# SCH_EDR_Project_2023-04-17.net
KiCad netlist of a schematic drawn in EasyEDA
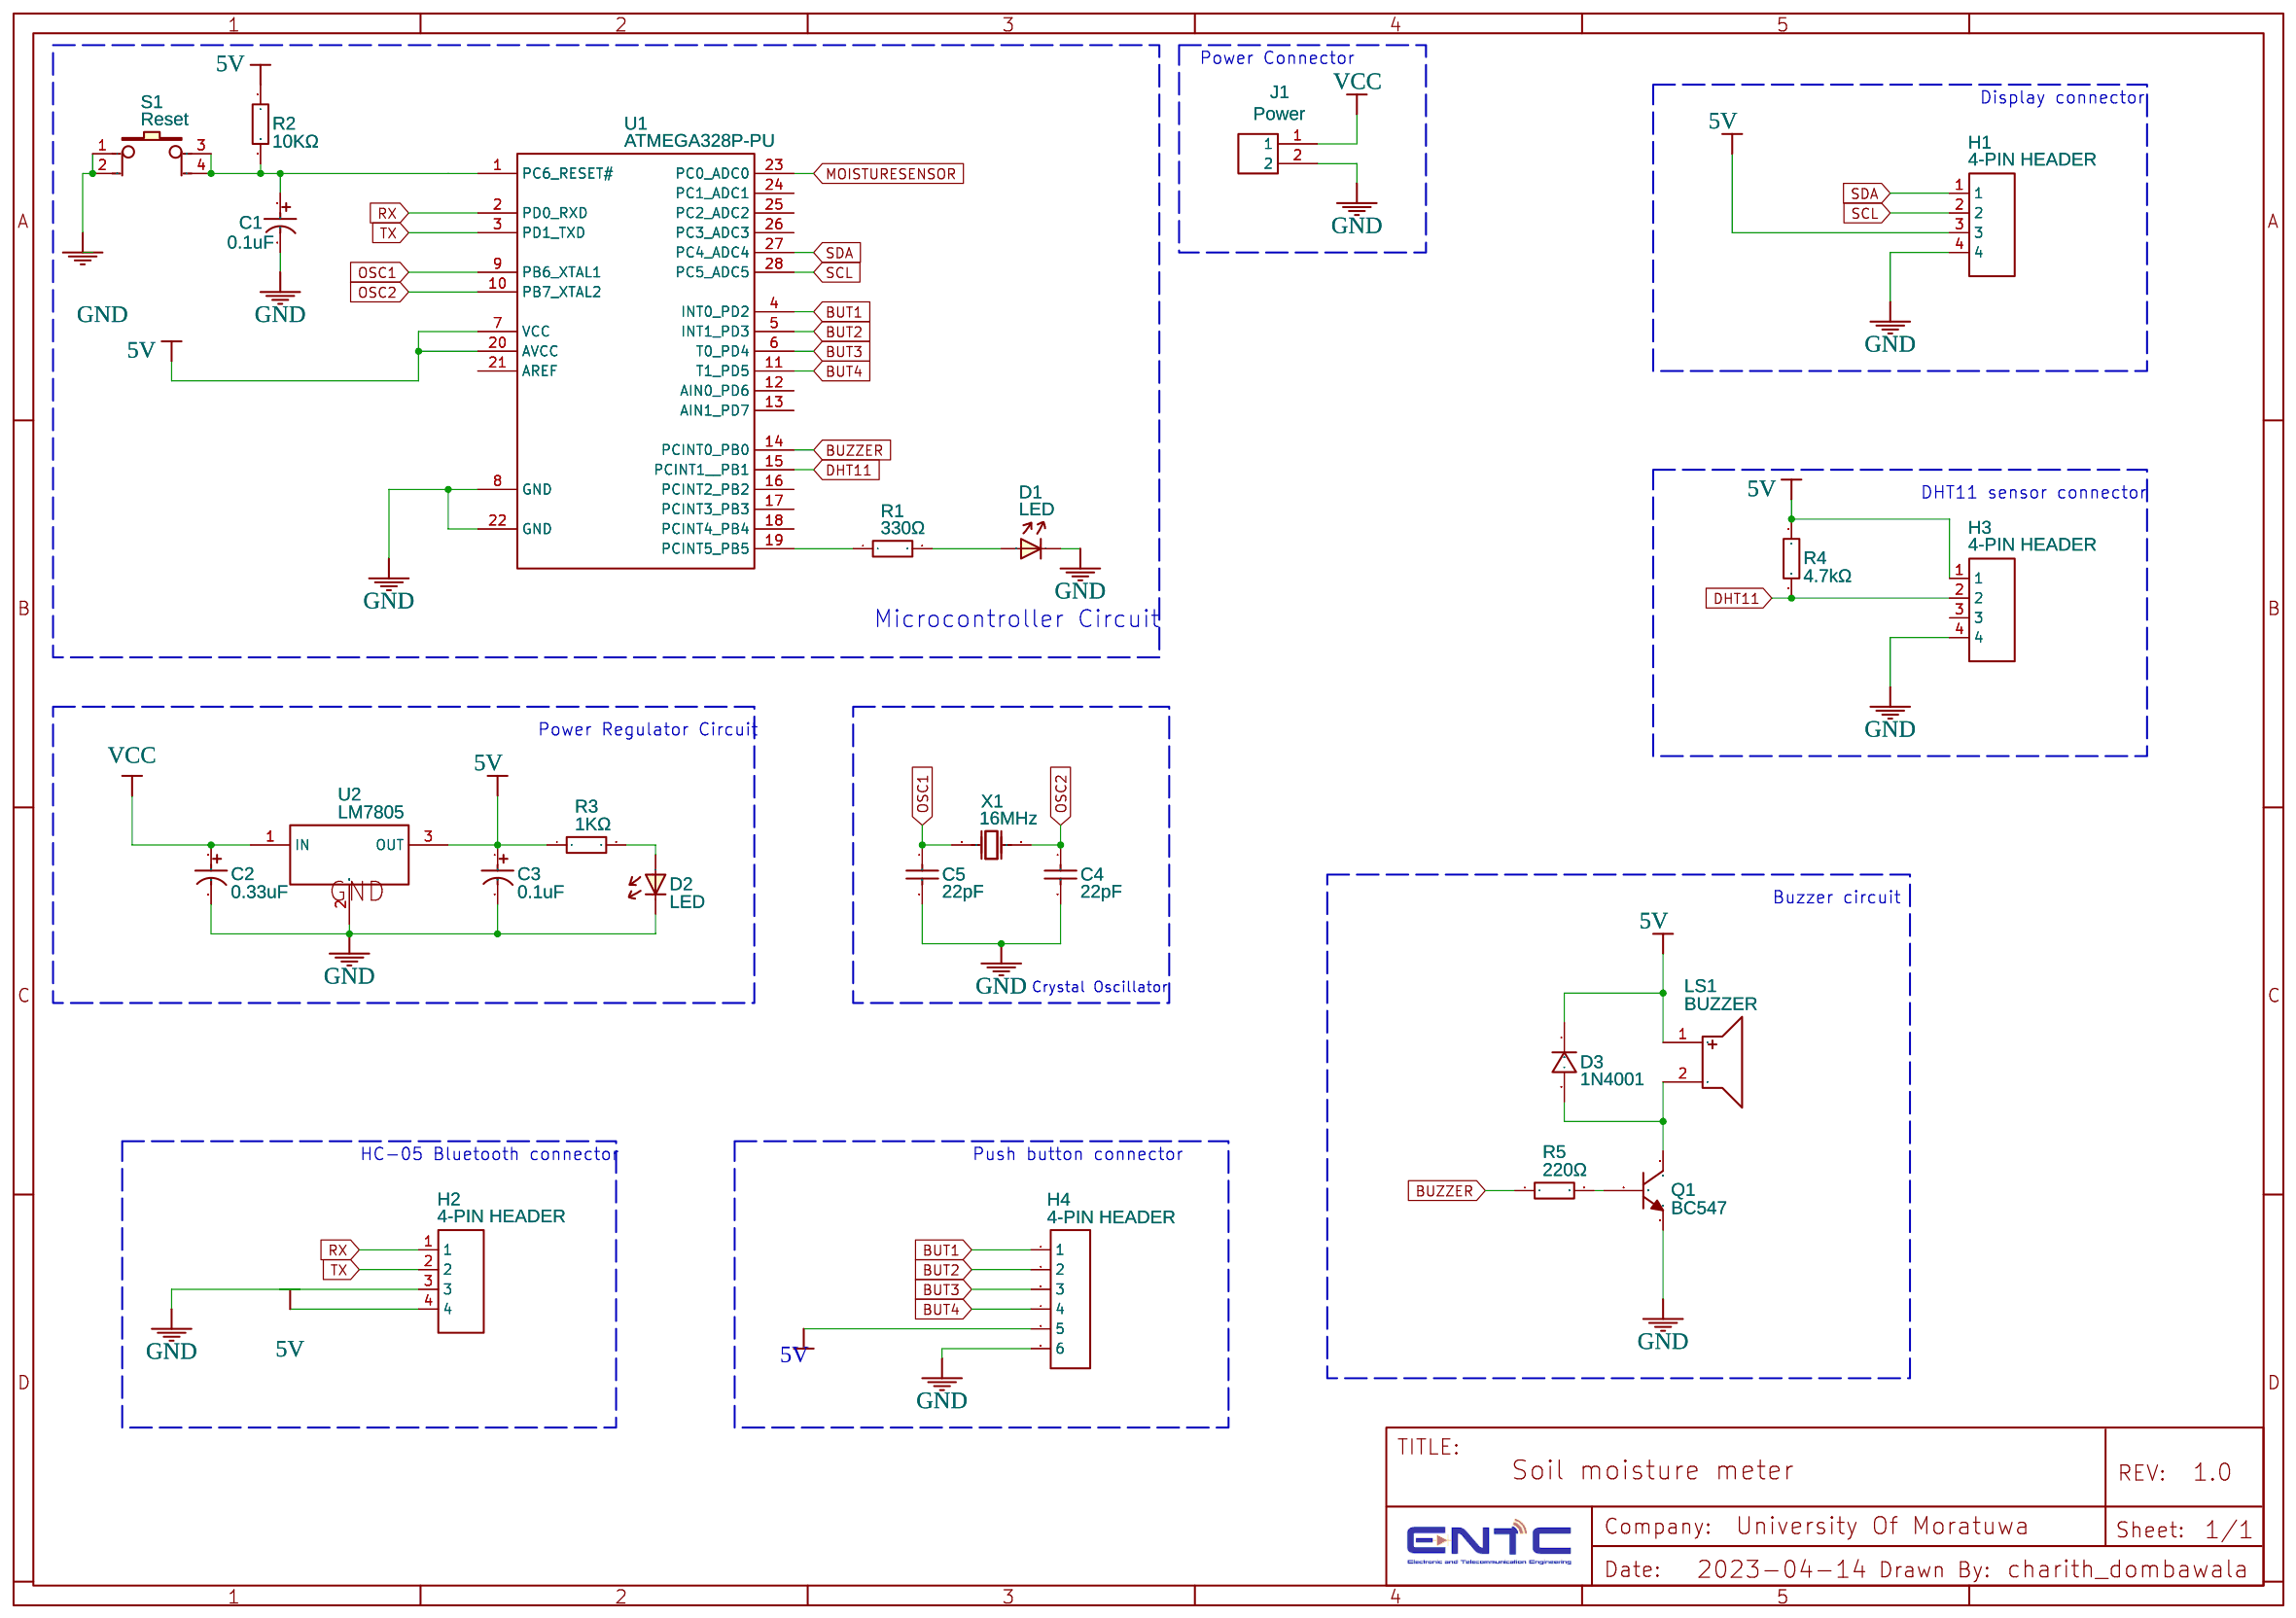
[diagram p0: schematic sheet]

(export (version "E")
  (design (tool "Eeschema 10.0.6"))
  (components
    (comp (ref "C1")
      (value "0.1uF")
      (fields (field (name "BOM_Manufacturer Part") "0.1UF 50V") (field (name "BOM_Supplier Part") "C28061"))
      (libsource (lib "") (part "0.1uF"))
    )
    (comp (ref "C2")
      (value "0.33uF")
      (fields
        (field (name "BOM_Manufacturer Part") "0.33uF 50V 5*11")
        (field (name "BOM_Supplier Part") "C45097")
      )
      (libsource (lib "") (part "0.33uF"))
    )
    (comp (ref "C3")
      (value "0.1uF")
      (fields (field (name "BOM_Manufacturer Part") "0.1UF 50V") (field (name "BOM_Supplier Part") "C28061"))
      (libsource (lib "") (part "0.1uF"))
    )
    (comp (ref "C4")
      (value "22pF")
      (fields
        (field (name "BOM_Manufacturer Part") "22pf/50V 10%")
        (field (name "BOM_Supplier Part") "C9316")
      )
      (libsource (lib "") (part "22pf/50V 10%"))
    )
    (comp (ref "C5")
      (value "22pF")
      (fields
        (field (name "BOM_Manufacturer Part") "22pf/50V 10%")
        (field (name "BOM_Supplier Part") "C9316")
      )
      (libsource (lib "") (part "22pf/50V 10%"))
    )
    (comp (ref "D1")
      (value "LED")
      (fields (field (name "Manufacturer Part") "5mm LED"))
      (libsource (lib "") (part "LED_1"))
    )
    (comp (ref "D2")
      (value "LED")
      (fields (field (name "Manufacturer Part") "5mm LED"))
      (libsource (lib "") (part "LED"))
    )
    (comp (ref "D3")
      (value "1N4001")
      (fields (field (name "BOM_Supplier Part") "C99656"))
      (libsource (lib "") (part "1N4001"))
    )
    (comp (ref "H1") (value "4-PIN HEADER") (libsource (lib "") (part "HEADER - HEADER-FEMALE-2.54_1X4")))
    (comp (ref "H2") (value "4-PIN HEADER") (libsource (lib "") (part "HEADER - HEADER-FEMALE-2.54_1X4")))
    (comp (ref "H3") (value "4-PIN HEADER") (libsource (lib "") (part "HEADER - HEADER-FEMALE-2.54_1X4")))
    (comp (ref "H4")
      (value "4-PIN HEADER")
      (fields (field (name "BOM_Supplier Part") "C40877"))
      (libsource (lib "") (part "HDR-F-2.54_1x6"))
    )
    (comp (ref "J1")
      (value "Power")
      (fields
        (field (name "BOM_Manufacturer Part") "XHB-2A Connector")
        (field (name "BOM_Supplier Part") "C57981")
      )
      (libsource (lib "") (part "JST_2 PIN"))
    )
    (comp (ref "LS1")
      (value "BUZZER")
      (fields
        (field (name "BOM_Manufacturer Part") "BUZZERHMB1206-03")
        (field (name "BOM_Supplier Part") "C96101")
      )
      (libsource (lib "") (part "BUZZER"))
    )
    (comp (ref "Q1")
      (value "BC547")
      (fields (field (name "BOM_Manufacturer Part") "BC547BTF") (field (name "BOM_Supplier Part") "C900798"))
      (libsource (lib "") (part "BC547BTF"))
    )
    (comp (ref "R1")
      (value "330Ω")
      (fields
        (field (name "BOM_Manufacturer Part") "MFR0W4F2200A50")
        (field (name "BOM_Supplier Part") "E57439")
      )
      (libsource (lib "") (part "RESISTOR_1"))
    )
    (comp (ref "R2")
      (value "10KΩ")
      (fields
        (field (name "BOM_Manufacturer Part") "MFR0W4F2200A50")
        (field (name "BOM_Supplier Part") "E57439")
      )
      (libsource (lib "") (part "RESISTOR"))
    )
    (comp (ref "R3")
      (value "1KΩ")
      (fields
        (field (name "BOM_Manufacturer Part") "MFR0W4F2200A50")
        (field (name "BOM_Supplier Part") "E57439")
      )
      (libsource (lib "") (part "RESISTOR_1"))
    )
    (comp (ref "R4")
      (value "4.7kΩ")
      (fields
        (field (name "BOM_Manufacturer Part") "MFR0W4F2200A50")
        (field (name "BOM_Supplier Part") "E57439")
      )
      (libsource (lib "") (part "RESISTOR"))
    )
    (comp (ref "R5")
      (value "220Ω")
      (fields
        (field (name "BOM_Manufacturer Part") "MFR0W4F2200A50")
        (field (name "BOM_Supplier Part") "E57439")
      )
      (libsource (lib "") (part "RESISTOR_1"))
    )
    (comp (ref "S1")
      (value "Reset")
      (fields
        (field (name "BOM_Manufacturer Part") "button6*6*8.5")
        (field (name "BOM_Supplier Part") "C59980")
      )
      (libsource (lib "") (part "Push_Button"))
    )
    (comp (ref "U1")
      (value "ATMEGA328P-PU")
      (fields (field (name "BOM_Supplier Part") "C33901"))
      (libsource (lib "") (part "ATMEGA328P-PU"))
    )
    (comp (ref "U2")
      (value "LM7805")
      (fields (field (name "BOM_Manufacturer Part") "L7805CV-DG") (field (name "BOM_Supplier Part") "C3795"))
      (libsource (lib "") (part "7805(TO-220)"))
    )
    (comp (ref "X1")
      (value "16MHz")
      (fields (field (name "BOM_Manufacturer Part") "ATS16A") (field (name "BOM_Supplier Part") "C1669847"))
      (libsource (lib "") (part "ATS16A"))
    )
  )
  (nets
    (net (code "1") (name "5V") (class "Default")
      (node (ref "C3") (pin "1") (pinfunction "1_1") (pintype "input"))
      (node (ref "D3") (pin "1") (pinfunction "C_1") (pintype "unspecified"))
      (node (ref "H1") (pin "3") (pinfunction "3_3") (pintype "unspecified"))
      (node (ref "H2") (pin "4") (pinfunction "4_4") (pintype "unspecified"))
      (node (ref "H3") (pin "1") (pinfunction "1_1") (pintype "unspecified"))
      (node (ref "H4") (pin "5") (pinfunction "5_5") (pintype "input"))
      (node (ref "LS1") (pin "1") (pinfunction "1_1") (pintype "unspecified"))
      (node (ref "R2") (pin "1") (pinfunction "1_1") (pintype "input"))
      (node (ref "R3") (pin "1") (pinfunction "1_1") (pintype "input"))
      (node (ref "R4") (pin "1") (pinfunction "1_1") (pintype "input"))
      (node (ref "U1") (pin "20") (pinfunction "AVCC_20") (pintype "passive"))
      (node (ref "U1") (pin "7") (pinfunction "VCC_7") (pintype "passive"))
      (node (ref "U2") (pin "3") (pinfunction "OUT_3") (pintype "passive"))
    )
    (net (code "2") (name "BUT1") (class "Default")
      (node (ref "H4") (pin "1") (pinfunction "1_1") (pintype "input"))
      (node (ref "U1") (pin "4") (pinfunction "INT0_PD2_4") (pintype "bidirectional"))
    )
    (net (code "3") (name "BUT2") (class "Default")
      (node (ref "H4") (pin "2") (pinfunction "2_2") (pintype "input"))
      (node (ref "U1") (pin "5") (pinfunction "INT1_PD3_5") (pintype "bidirectional"))
    )
    (net (code "4") (name "BUT3") (class "Default")
      (node (ref "H4") (pin "3") (pinfunction "3_3") (pintype "input"))
      (node (ref "U1") (pin "6") (pinfunction "T0_PD4_6") (pintype "bidirectional"))
    )
    (net (code "5") (name "BUT4") (class "Default")
      (node (ref "H4") (pin "4") (pinfunction "4_4") (pintype "input"))
      (node (ref "U1") (pin "11") (pinfunction "T1_PD5_11") (pintype "bidirectional"))
    )
    (net (code "6") (name "BUZZER") (class "Default")
      (node (ref "R5") (pin "1") (pinfunction "1_1") (pintype "input"))
      (node (ref "U1") (pin "14") (pinfunction "PCINT0_PB0_14") (pintype "bidirectional"))
    )
    (net (code "7") (name "DHT11") (class "Default")
      (node (ref "H3") (pin "2") (pinfunction "2_2") (pintype "unspecified"))
      (node (ref "R4") (pin "2") (pinfunction "2_2") (pintype "input"))
      (node (ref "U1") (pin "15") (pinfunction "PCINT1__PB1_15") (pintype "bidirectional"))
    )
    (net (code "8") (name "GND") (class "Default")
      (node (ref "C1") (pin "2") (pinfunction "2_2") (pintype "input"))
      (node (ref "C2") (pin "2") (pinfunction "2_2") (pintype "input"))
      (node (ref "C3") (pin "2") (pinfunction "2_2") (pintype "input"))
      (node (ref "C4") (pin "2") (pinfunction "2_2") (pintype "input"))
      (node (ref "C5") (pin "2") (pinfunction "2_2") (pintype "input"))
      (node (ref "D1") (pin "2") (pinfunction "2_2") (pintype "unspecified"))
      (node (ref "D2") (pin "2") (pinfunction "2_2") (pintype "unspecified"))
      (node (ref "H1") (pin "4") (pinfunction "4_4") (pintype "unspecified"))
      (node (ref "H2") (pin "3") (pinfunction "3_3") (pintype "unspecified"))
      (node (ref "H3") (pin "4") (pinfunction "4_4") (pintype "unspecified"))
      (node (ref "H4") (pin "6") (pinfunction "6_6") (pintype "input"))
      (node (ref "J1") (pin "2") (pinfunction "2_2") (pintype "unspecified"))
      (node (ref "Q1") (pin "3") (pinfunction "E_3") (pintype "unspecified"))
      (node (ref "S1") (pin "1") (pinfunction "1_1") (pintype "input"))
      (node (ref "S1") (pin "2") (pinfunction "2_2") (pintype "input"))
      (node (ref "U1") (pin "22") (pinfunction "GND_22") (pintype "passive"))
      (node (ref "U1") (pin "8") (pinfunction "GND_8") (pintype "passive"))
      (node (ref "U2") (pin "2") (pinfunction "GND_2") (pintype "passive"))
    )
    (net (code "9") (name "MOISTURESENSOR") (class "Default")
      (node (ref "U1") (pin "23") (pinfunction "PC0_ADC0_23") (pintype "bidirectional"))
    )
    (net (code "10") (name "Net-(D1-Pad1)") (class "Default")
      (node (ref "D1") (pin "1") (pinfunction "1_1") (pintype "unspecified"))
      (node (ref "R1") (pin "2") (pinfunction "2_2") (pintype "input"))
    )
    (net (code "11") (name "Net-(D2-Pad1)") (class "Default")
      (node (ref "D2") (pin "1") (pinfunction "1_1") (pintype "unspecified"))
      (node (ref "R3") (pin "2") (pinfunction "2_2") (pintype "input"))
    )
    (net (code "12") (name "Net-(D3-A)") (class "Default")
      (node (ref "D3") (pin "2") (pinfunction "A_2") (pintype "unspecified"))
      (node (ref "LS1") (pin "2") (pinfunction "2_2") (pintype "unspecified"))
      (node (ref "Q1") (pin "1") (pinfunction "C_1") (pintype "unspecified"))
    )
    (net (code "13") (name "Net-(Q1-B)") (class "Default")
      (node (ref "Q1") (pin "2") (pinfunction "B_2") (pintype "unspecified"))
      (node (ref "R5") (pin "2") (pinfunction "2_2") (pintype "input"))
    )
    (net (code "14") (name "Net-(U1-PC6_RESET#)") (class "Default")
      (node (ref "C1") (pin "1") (pinfunction "1_1") (pintype "input"))
      (node (ref "R2") (pin "2") (pinfunction "2_2") (pintype "input"))
      (node (ref "S1") (pin "3") (pinfunction "3_3") (pintype "input"))
      (node (ref "S1") (pin "4") (pinfunction "4_4") (pintype "input"))
      (node (ref "U1") (pin "1") (pinfunction "PC6_RESET#_1") (pintype "bidirectional"))
    )
    (net (code "15") (name "Net-(U1-PCINT5_PB5)") (class "Default")
      (node (ref "R1") (pin "1") (pinfunction "1_1") (pintype "input"))
      (node (ref "U1") (pin "19") (pinfunction "PCINT5_PB5_19") (pintype "bidirectional"))
    )
    (net (code "16") (name "OSC1") (class "Default")
      (node (ref "C5") (pin "1") (pinfunction "1_1") (pintype "input"))
      (node (ref "U1") (pin "9") (pinfunction "PB6_XTAL1_9") (pintype "bidirectional"))
      (node (ref "X1") (pin "1") (pinfunction "1_1") (pintype "input"))
    )
    (net (code "17") (name "OSC2") (class "Default")
      (node (ref "C4") (pin "1") (pinfunction "1_1") (pintype "input"))
      (node (ref "U1") (pin "10") (pinfunction "PB7_XTAL2_10") (pintype "bidirectional"))
      (node (ref "X1") (pin "2") (pinfunction "2_2") (pintype "input"))
    )
    (net (code "18") (name "RX") (class "Default")
      (node (ref "H2") (pin "1") (pinfunction "1_1") (pintype "unspecified"))
      (node (ref "U1") (pin "2") (pinfunction "PD0_RXD_2") (pintype "bidirectional"))
    )
    (net (code "19") (name "SCL") (class "Default")
      (node (ref "H1") (pin "2") (pinfunction "2_2") (pintype "unspecified"))
      (node (ref "U1") (pin "28") (pinfunction "PC5_ADC5_28") (pintype "bidirectional"))
    )
    (net (code "20") (name "SDA") (class "Default")
      (node (ref "H1") (pin "1") (pinfunction "1_1") (pintype "unspecified"))
      (node (ref "U1") (pin "27") (pinfunction "PC4_ADC4_27") (pintype "bidirectional"))
    )
    (net (code "21") (name "TX") (class "Default")
      (node (ref "H2") (pin "2") (pinfunction "2_2") (pintype "unspecified"))
      (node (ref "U1") (pin "3") (pinfunction "PD1_TXD_3") (pintype "bidirectional"))
    )
    (net (code "22") (name "VCC") (class "Default")
      (node (ref "C2") (pin "1") (pinfunction "1_1") (pintype "input"))
      (node (ref "J1") (pin "1") (pinfunction "1_1") (pintype "unspecified"))
      (node (ref "U2") (pin "1") (pinfunction "IN_1") (pintype "passive"))
    )
    (net (code "23") (name "unconnected-(H3-Pad3)") (class "Default")
      (node (ref "H3") (pin "3") (pinfunction "3_3") (pintype "unspecified"))
    )
    (net (code "24") (name "unconnected-(U1-AIN0_PD6-Pad12)") (class "Default")
      (node (ref "U1") (pin "12") (pinfunction "AIN0_PD6_12") (pintype "bidirectional"))
    )
    (net (code "25") (name "unconnected-(U1-AIN1_PD7-Pad13)") (class "Default")
      (node (ref "U1") (pin "13") (pinfunction "AIN1_PD7_13") (pintype "bidirectional"))
    )
    (net (code "26") (name "unconnected-(U1-AREF-Pad21)") (class "Default")
      (node (ref "U1") (pin "21") (pinfunction "AREF_21") (pintype "passive"))
    )
    (net (code "27") (name "unconnected-(U1-PC1_ADC1-Pad24)") (class "Default")
      (node (ref "U1") (pin "24") (pinfunction "PC1_ADC1_24") (pintype "bidirectional"))
    )
    (net (code "28") (name "unconnected-(U1-PC2_ADC2-Pad25)") (class "Default")
      (node (ref "U1") (pin "25") (pinfunction "PC2_ADC2_25") (pintype "bidirectional"))
    )
    (net (code "29") (name "unconnected-(U1-PC3_ADC3-Pad26)") (class "Default")
      (node (ref "U1") (pin "26") (pinfunction "PC3_ADC3_26") (pintype "bidirectional"))
    )
    (net (code "30") (name "unconnected-(U1-PCINT2_PB2-Pad16)") (class "Default")
      (node (ref "U1") (pin "16") (pinfunction "PCINT2_PB2_16") (pintype "bidirectional"))
    )
    (net (code "31") (name "unconnected-(U1-PCINT3_PB3-Pad17)") (class "Default")
      (node (ref "U1") (pin "17") (pinfunction "PCINT3_PB3_17") (pintype "bidirectional"))
    )
    (net (code "32") (name "unconnected-(U1-PCINT4_PB4-Pad18)") (class "Default")
      (node (ref "U1") (pin "18") (pinfunction "PCINT4_PB4_18") (pintype "bidirectional"))
    )
  )
)
